# TopLevel.net
KiCad netlist of a schematic drawn in Altium Designer
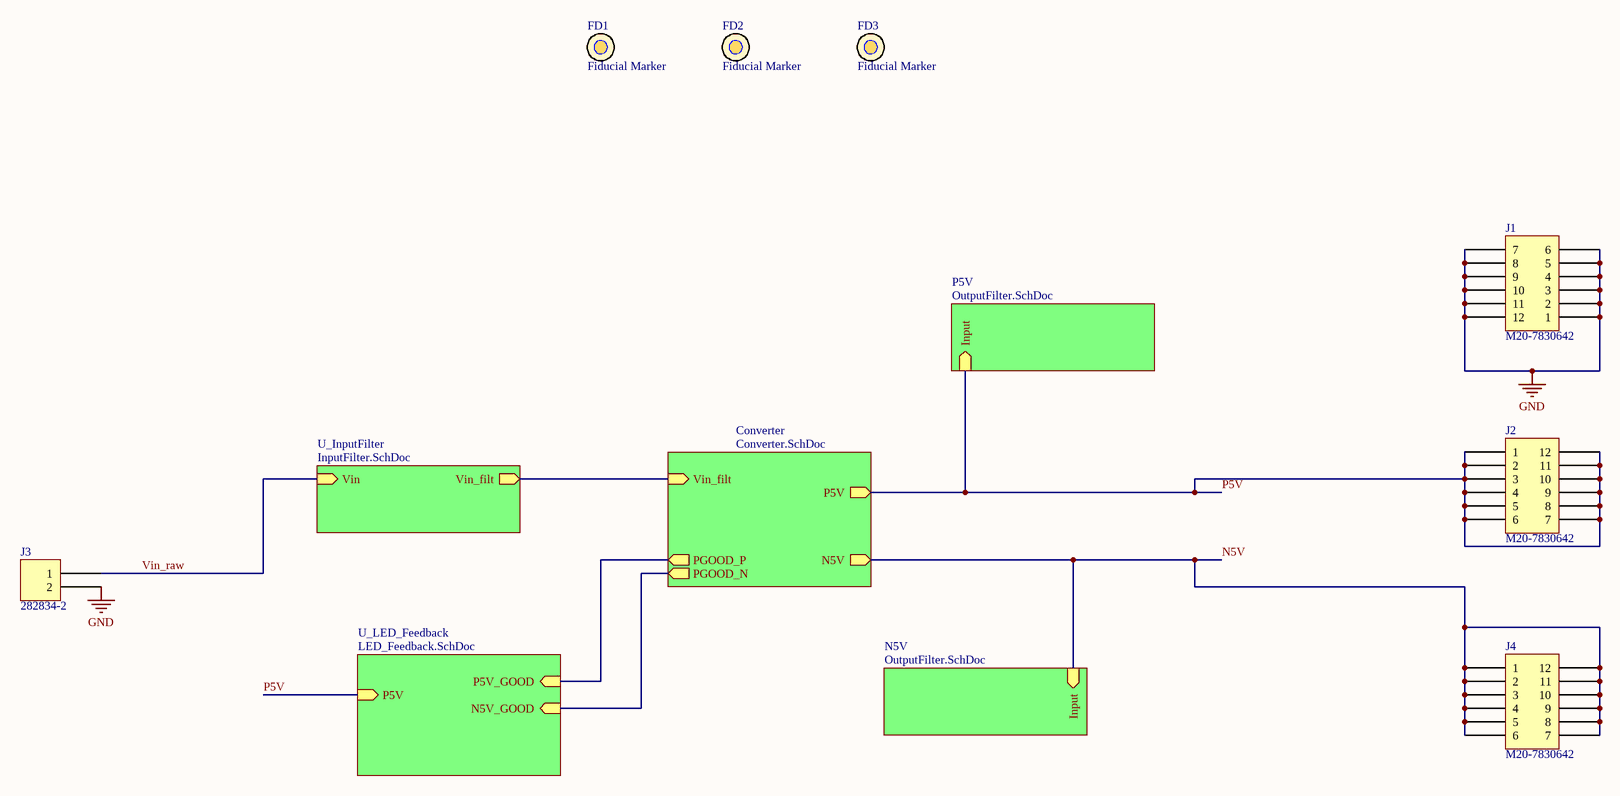
[diagram p0: TopLevel.SchDoc]

(export (version "E")
  (design (tool "Eeschema 10.0.6"))
  (components
    (comp (ref "FD1")
      (value "Fiducial Marker")
      (footprint "FIDUCIAL")
      (libsource (lib "Common") (part "Fiducial"))
    )
    (comp (ref "FD2")
      (value "Fiducial Marker")
      (footprint "FIDUCIAL")
      (libsource (lib "Common") (part "Fiducial"))
    )
    (comp (ref "FD3")
      (value "Fiducial Marker")
      (footprint "FIDUCIAL")
      (libsource (lib "Common") (part "Fiducial"))
    )
    (comp (ref "J1")
      (value "M20-7830642")
      (footprint "HARWIN M20-7830645")
      (description "CONN RCPT 12POS 0.1 GOLD PCB")
      (fields (field (name "MANUFACTURER") "Harwin Inc."))
      (libsource (lib "Celestial Altium Library - altium_library") (part "2X6 PIN DU"))
    )
    (comp (ref "J2")
      (value "M20-7830642")
      (footprint "HARWIN M20-7830645")
      (description "CONN RCPT 12POS 0.1 GOLD PCB")
      (fields (field (name "MANUFACTURER") "Harwin Inc."))
      (libsource (lib "") (part "2X6 PIN DU_1"))
    )
    (comp (ref "J3")
      (value "282834-2")
      (footprint "TE 282834-2")
      (description "TERM BLK 2P SIDE ENT 2.54MM PCB")
      (fields (field (name "MANUFACTURER") "TE Connectivity AMP Connectors") (field (name "VOLTAGE") "150V"))
      (libsource (lib "Celestial Altium Library - altium_library") (part "2 Pin"))
    )
    (comp (ref "J4")
      (value "M20-7830642")
      (footprint "HARWIN M20-7830645")
      (description "CONN RCPT 12POS 0.1 GOLD PCB")
      (fields (field (name "MANUFACTURER") "Harwin Inc."))
      (libsource (lib "") (part "2X6 PIN DU_1"))
    )
  )
  (nets
    (net (code "1") (name "/N5V") (class "Default")
      (node (ref "J4") (pin "1") (pinfunction "1_1") (pintype "passive"))
      (node (ref "J4") (pin "10") (pinfunction "10_10") (pintype "passive"))
      (node (ref "J4") (pin "11") (pinfunction "11_11") (pintype "passive"))
      (node (ref "J4") (pin "12") (pinfunction "12_12") (pintype "passive"))
      (node (ref "J4") (pin "2") (pinfunction "2_2") (pintype "passive"))
      (node (ref "J4") (pin "3") (pinfunction "3_3") (pintype "passive"))
      (node (ref "J4") (pin "4") (pinfunction "4_4") (pintype "passive"))
      (node (ref "J4") (pin "5") (pinfunction "5_5") (pintype "passive"))
      (node (ref "J4") (pin "6") (pinfunction "6_6") (pintype "passive"))
      (node (ref "J4") (pin "7") (pinfunction "7_7") (pintype "passive"))
      (node (ref "J4") (pin "8") (pinfunction "8_8") (pintype "passive"))
      (node (ref "J4") (pin "9") (pinfunction "9_9") (pintype "passive"))
    )
    (net (code "2") (name "/P5V") (class "Default")
      (node (ref "J2") (pin "1") (pinfunction "1_1") (pintype "passive"))
      (node (ref "J2") (pin "10") (pinfunction "10_10") (pintype "passive"))
      (node (ref "J2") (pin "11") (pinfunction "11_11") (pintype "passive"))
      (node (ref "J2") (pin "12") (pinfunction "12_12") (pintype "passive"))
      (node (ref "J2") (pin "2") (pinfunction "2_2") (pintype "passive"))
      (node (ref "J2") (pin "3") (pinfunction "3_3") (pintype "passive"))
      (node (ref "J2") (pin "4") (pinfunction "4_4") (pintype "passive"))
      (node (ref "J2") (pin "5") (pinfunction "5_5") (pintype "passive"))
      (node (ref "J2") (pin "6") (pinfunction "6_6") (pintype "passive"))
      (node (ref "J2") (pin "7") (pinfunction "7_7") (pintype "passive"))
      (node (ref "J2") (pin "8") (pinfunction "8_8") (pintype "passive"))
      (node (ref "J2") (pin "9") (pinfunction "9_9") (pintype "passive"))
    )
    (net (code "6") (name "/Vin_raw") (class "Default")
      (node (ref "J3") (pin "1") (pinfunction "1_1") (pintype "passive"))
    )
    (net (code "7") (name "GND") (class "Default")
      (node (ref "J1") (pin "1") (pinfunction "1_1") (pintype "passive"))
      (node (ref "J1") (pin "10") (pinfunction "10_10") (pintype "passive"))
      (node (ref "J1") (pin "11") (pinfunction "11_11") (pintype "passive"))
      (node (ref "J1") (pin "12") (pinfunction "12_12") (pintype "passive"))
      (node (ref "J1") (pin "2") (pinfunction "2_2") (pintype "passive"))
      (node (ref "J1") (pin "3") (pinfunction "3_3") (pintype "passive"))
      (node (ref "J1") (pin "4") (pinfunction "4_4") (pintype "passive"))
      (node (ref "J1") (pin "5") (pinfunction "5_5") (pintype "passive"))
      (node (ref "J1") (pin "6") (pinfunction "6_6") (pintype "passive"))
      (node (ref "J1") (pin "7") (pinfunction "7_7") (pintype "passive"))
      (node (ref "J1") (pin "8") (pinfunction "8_8") (pintype "passive"))
      (node (ref "J1") (pin "9") (pinfunction "9_9") (pintype "passive"))
      (node (ref "J3") (pin "2") (pinfunction "2_2") (pintype "passive"))
    )
  )
)
